# 3_ports.net
KiCad netlist of a schematic drawn in Altium Designer
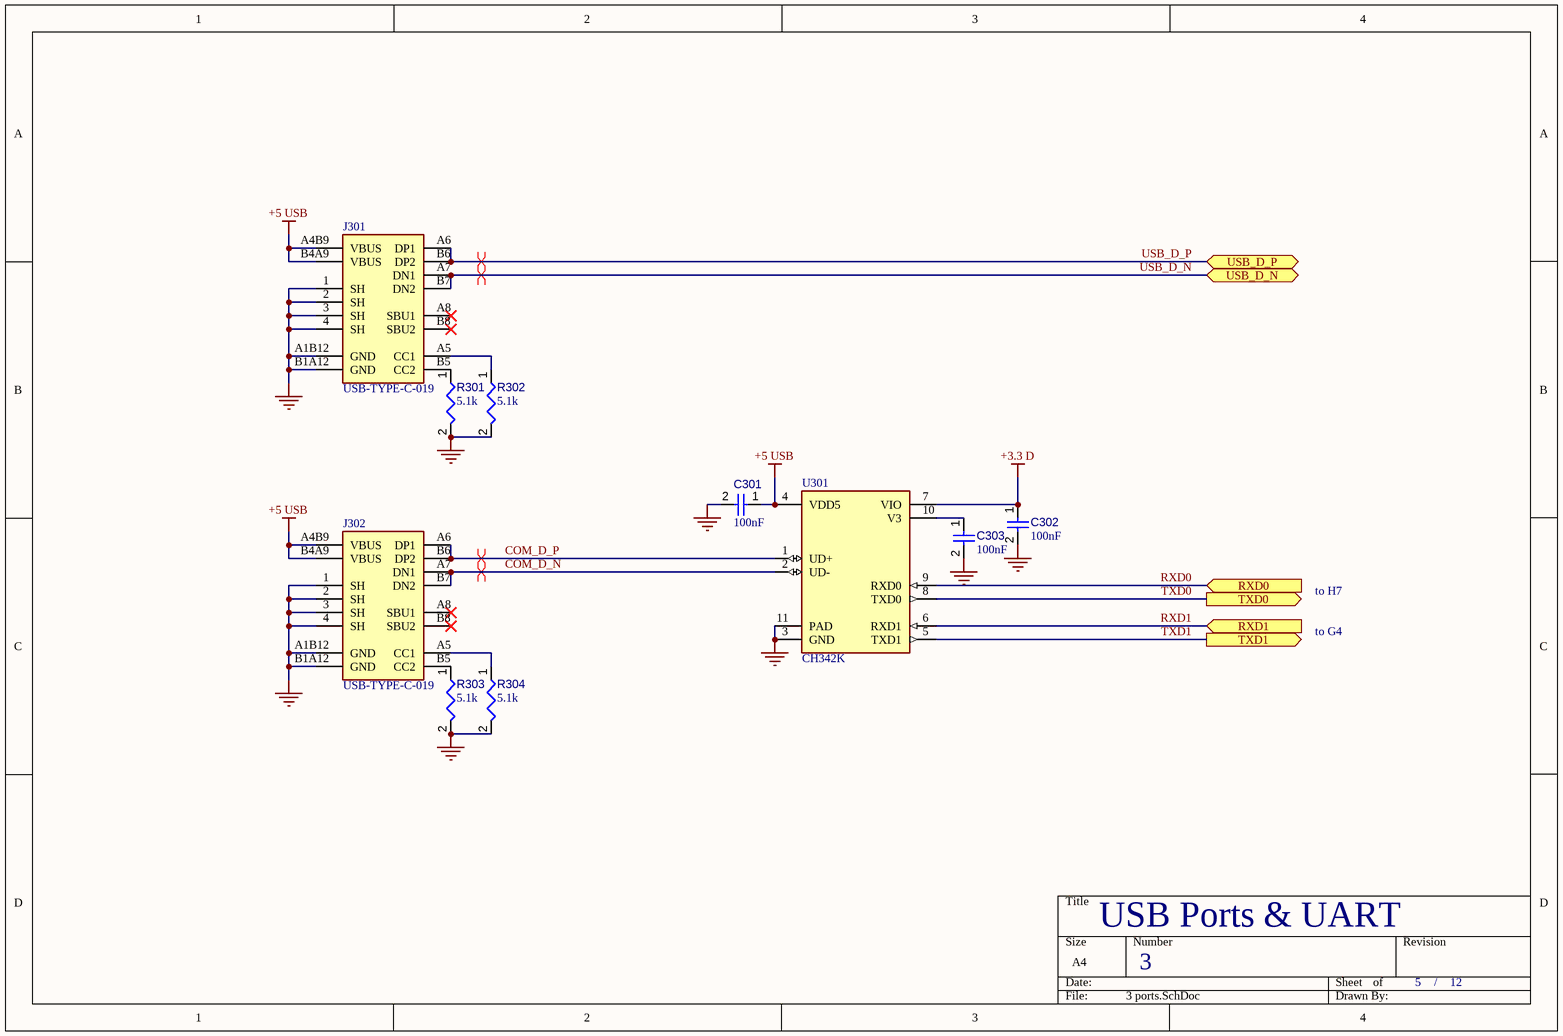
[diagram p0: 3 ports.SchDoc]

(export (version "E")
  (design (tool "Eeschema 10.0.6"))
  (components
    (comp (ref "C301")
      (value "100nF")
      (footprint "CAPC0402(1005)60_L")
      (description "Chip Capacitor, 100nF +/-20%, 25V, 0402, Thickness 0.6 mm")
      (fields (field (name "TOLERANCE") "10%") (field (name "Comment") "Capacitor 100nF +/-20% 25V 0402"))
      (libsource (lib "UBC Uncrewed Aircraft Systems") (part "CAP-NP-2"))
    )
    (comp (ref "C302")
      (value "100nF")
      (footprint "CAPC0402(1005)60_L")
      (description "Chip Capacitor, 100nF +/-20%, 25V, 0402, Thickness 0.6 mm")
      (fields (field (name "TOLERANCE") "10%") (field (name "Comment") "Capacitor 100nF +/-20% 25V 0402"))
      (libsource (lib "UBC Uncrewed Aircraft Systems") (part "CAP-NP-2"))
    )
    (comp (ref "C303")
      (value "100nF")
      (footprint "CAPC0402(1005)60_L")
      (description "Chip Capacitor, 100nF +/-20%, 25V, 0402, Thickness 0.6 mm")
      (fields (field (name "TOLERANCE") "10%") (field (name "Comment") "Capacitor 100nF +/-20% 25V 0402"))
      (libsource (lib "UBC Uncrewed Aircraft Systems") (part "CAP-NP-2"))
    )
    (comp (ref "J301")
      (value "USB-TYPE-C-019")
      (footprint "USB-TYPE-C-12+4P")
      (fields (field (name "MANUFACTURER") "DEALON(德艺隆)"))
      (libsource (lib "JLCPCB Library") (part "USB-TYPE-C-019"))
    )
    (comp (ref "J302")
      (value "USB-TYPE-C-019")
      (footprint "USB-TYPE-C-12+4P")
      (fields (field (name "MANUFACTURER") "DEALON(德艺隆)"))
      (libsource (lib "JLCPCB Library") (part "USB-TYPE-C-019"))
    )
    (comp (ref "R301")
      (value "5.1k")
      (footprint "RESC0402(1005)_L")
      (description "Chip Resistor, 5.1 kOhms, +/-1 %, 63 mW, -55 to 155 degC, 0402")
      (fields (field (name "POWER") "63mW") (field (name "TOLERANCE") "1%"))
      (libsource (lib "UBC Uncrewed Aircraft Systems") (part "RES-2"))
    )
    (comp (ref "R302")
      (value "5.1k")
      (footprint "RESC0402(1005)_L")
      (description "Chip Resistor, 5.1 kOhms, +/-1 %, 63 mW, -55 to 155 degC, 0402")
      (fields (field (name "POWER") "63mW") (field (name "TOLERANCE") "1%"))
      (libsource (lib "UBC Uncrewed Aircraft Systems") (part "RES-2"))
    )
    (comp (ref "R303")
      (value "5.1k")
      (footprint "RESC0402(1005)_L")
      (description "Chip Resistor, 5.1 kOhms, +/-1 %, 63 mW, -55 to 155 degC, 0402")
      (fields (field (name "POWER") "63mW") (field (name "TOLERANCE") "1%"))
      (libsource (lib "UBC Uncrewed Aircraft Systems") (part "RES-2"))
    )
    (comp (ref "R304")
      (value "5.1k")
      (footprint "RESC0402(1005)_L")
      (description "Chip Resistor, 5.1 kOhms, +/-1 %, 63 mW, -55 to 155 degC, 0402")
      (fields (field (name "POWER") "63mW") (field (name "TOLERANCE") "1%"))
      (libsource (lib "UBC Uncrewed Aircraft Systems") (part "RES-2"))
    )
    (comp (ref "U301")
      (value "CH342K")
      (footprint "SSOP-10_L5.0-W3.9-P1.00-LS6.0-BL-EP")
      (description "ESSOP-10-150mil USB Converters ROHS")
      (libsource (lib "JLCPCB Library") (part "CH342K"))
    )
  )
  (nets
    (net (code "1") (name "+3.3 D") (class "Default")
      (node (ref "C302") (pin "1") (pinfunction "1_1") (pintype "passive"))
      (node (ref "U301") (pin "7") (pinfunction "VIO_7") (pintype "power_in"))
    )
    (net (code "2") (name "+5 USB") (class "Default")
      (node (ref "C301") (pin "1") (pinfunction "1_1") (pintype "passive"))
      (node (ref "J301") (pin "A4B9") (pinfunction "VBUS_A4B9") (pintype "power_in"))
      (node (ref "J301") (pin "B4A9") (pinfunction "VBUS_B4A9") (pintype "power_in"))
      (node (ref "J302") (pin "A4B9") (pinfunction "VBUS_A4B9") (pintype "power_in"))
      (node (ref "J302") (pin "B4A9") (pinfunction "VBUS_B4A9") (pintype "power_in"))
      (node (ref "U301") (pin "4") (pinfunction "VDD5_4") (pintype "power_in"))
    )
    (net (code "3") (name "/COM_D_N") (class "Default")
      (node (ref "J302") (pin "A7") (pinfunction "DN1_A7") (pintype "passive"))
      (node (ref "J302") (pin "B7") (pinfunction "DN2_B7") (pintype "passive"))
      (node (ref "U301") (pin "2") (pinfunction "UD-_2") (pintype "bidirectional"))
    )
    (net (code "4") (name "/COM_D_P") (class "Default")
      (node (ref "J302") (pin "A6") (pinfunction "DP1_A6") (pintype "passive"))
      (node (ref "J302") (pin "B6") (pinfunction "DP2_B6") (pintype "passive"))
      (node (ref "U301") (pin "1") (pinfunction "UD+_1") (pintype "bidirectional"))
    )
    (net (code "5") (name "/RXD0") (class "Default")
      (node (ref "U301") (pin "9") (pinfunction "RXD0_9") (pintype "input"))
    )
    (net (code "6") (name "/RXD1") (class "Default")
      (node (ref "U301") (pin "6") (pinfunction "RXD1_6") (pintype "input"))
    )
    (net (code "7") (name "/TXD0") (class "Default")
      (node (ref "U301") (pin "8") (pinfunction "TXD0_8") (pintype "output"))
    )
    (net (code "8") (name "/TXD1") (class "Default")
      (node (ref "U301") (pin "5") (pinfunction "TXD1_5") (pintype "output"))
    )
    (net (code "9") (name "/USB_D_N") (class "Default")
      (node (ref "J301") (pin "A7") (pinfunction "DN1_A7") (pintype "passive"))
      (node (ref "J301") (pin "B7") (pinfunction "DN2_B7") (pintype "passive"))
    )
    (net (code "10") (name "/USB_D_P") (class "Default")
      (node (ref "J301") (pin "A6") (pinfunction "DP1_A6") (pintype "passive"))
      (node (ref "J301") (pin "B6") (pinfunction "DP2_B6") (pintype "passive"))
    )
    (net (code "11") (name "GND") (class "Default")
      (node (ref "C301") (pin "2") (pinfunction "2_2") (pintype "passive"))
      (node (ref "C302") (pin "2") (pinfunction "2_2") (pintype "passive"))
      (node (ref "C303") (pin "2") (pinfunction "2_2") (pintype "passive"))
      (node (ref "J301") (pin "1") (pinfunction "SH_1") (pintype "passive"))
      (node (ref "J301") (pin "2") (pinfunction "SH_2") (pintype "passive"))
      (node (ref "J301") (pin "3") (pinfunction "SH_3") (pintype "passive"))
      (node (ref "J301") (pin "4") (pinfunction "SH_4") (pintype "passive"))
      (node (ref "J301") (pin "A1B12") (pinfunction "GND_A1B12") (pintype "power_in"))
      (node (ref "J301") (pin "B1A12") (pinfunction "GND_B1A12") (pintype "power_in"))
      (node (ref "J302") (pin "1") (pinfunction "SH_1") (pintype "passive"))
      (node (ref "J302") (pin "2") (pinfunction "SH_2") (pintype "passive"))
      (node (ref "J302") (pin "3") (pinfunction "SH_3") (pintype "passive"))
      (node (ref "J302") (pin "4") (pinfunction "SH_4") (pintype "passive"))
      (node (ref "J302") (pin "A1B12") (pinfunction "GND_A1B12") (pintype "power_in"))
      (node (ref "J302") (pin "B1A12") (pinfunction "GND_B1A12") (pintype "power_in"))
      (node (ref "R301") (pin "2") (pinfunction "2_2") (pintype "passive"))
      (node (ref "R302") (pin "2") (pinfunction "2_2") (pintype "passive"))
      (node (ref "R303") (pin "2") (pinfunction "2_2") (pintype "passive"))
      (node (ref "R304") (pin "2") (pinfunction "2_2") (pintype "passive"))
      (node (ref "U301") (pin "11") (pinfunction "PAD_11") (pintype "power_in"))
      (node (ref "U301") (pin "3") (pinfunction "GND_3") (pintype "power_in"))
    )
    (net (code "12") (name "Net-(J301-CC1)") (class "Default")
      (node (ref "J301") (pin "A5") (pinfunction "CC1_A5") (pintype "passive"))
      (node (ref "R302") (pin "1") (pinfunction "1_1") (pintype "passive"))
    )
    (net (code "13") (name "Net-(J301-CC2)") (class "Default")
      (node (ref "J301") (pin "B5") (pinfunction "CC2_B5") (pintype "passive"))
      (node (ref "R301") (pin "1") (pinfunction "1_1") (pintype "passive"))
    )
    (net (code "14") (name "Net-(J302-CC1)") (class "Default")
      (node (ref "J302") (pin "A5") (pinfunction "CC1_A5") (pintype "passive"))
      (node (ref "R304") (pin "1") (pinfunction "1_1") (pintype "passive"))
    )
    (net (code "15") (name "Net-(J302-CC2)") (class "Default")
      (node (ref "J302") (pin "B5") (pinfunction "CC2_B5") (pintype "passive"))
      (node (ref "R303") (pin "1") (pinfunction "1_1") (pintype "passive"))
    )
    (net (code "16") (name "Net-(U301-V3)") (class "Default")
      (node (ref "C303") (pin "1") (pinfunction "1_1") (pintype "passive"))
      (node (ref "U301") (pin "10") (pinfunction "V3_10") (pintype "power_in"))
    )
    (net (code "17") (name "unconnected-(J301-SBU1-PadA8)") (class "Default")
      (node (ref "J301") (pin "A8") (pinfunction "SBU1_A8") (pintype "passive+no_connect"))
    )
    (net (code "18") (name "unconnected-(J301-SBU2-PadB8)") (class "Default")
      (node (ref "J301") (pin "B8") (pinfunction "SBU2_B8") (pintype "passive+no_connect"))
    )
    (net (code "19") (name "unconnected-(J302-SBU1-PadA8)") (class "Default")
      (node (ref "J302") (pin "A8") (pinfunction "SBU1_A8") (pintype "passive+no_connect"))
    )
    (net (code "20") (name "unconnected-(J302-SBU2-PadB8)") (class "Default")
      (node (ref "J302") (pin "B8") (pinfunction "SBU2_B8") (pintype "passive+no_connect"))
    )
  )
)
